# Main_Board_Motor_Control.net
KiCad netlist of a schematic drawn in Altium Designer
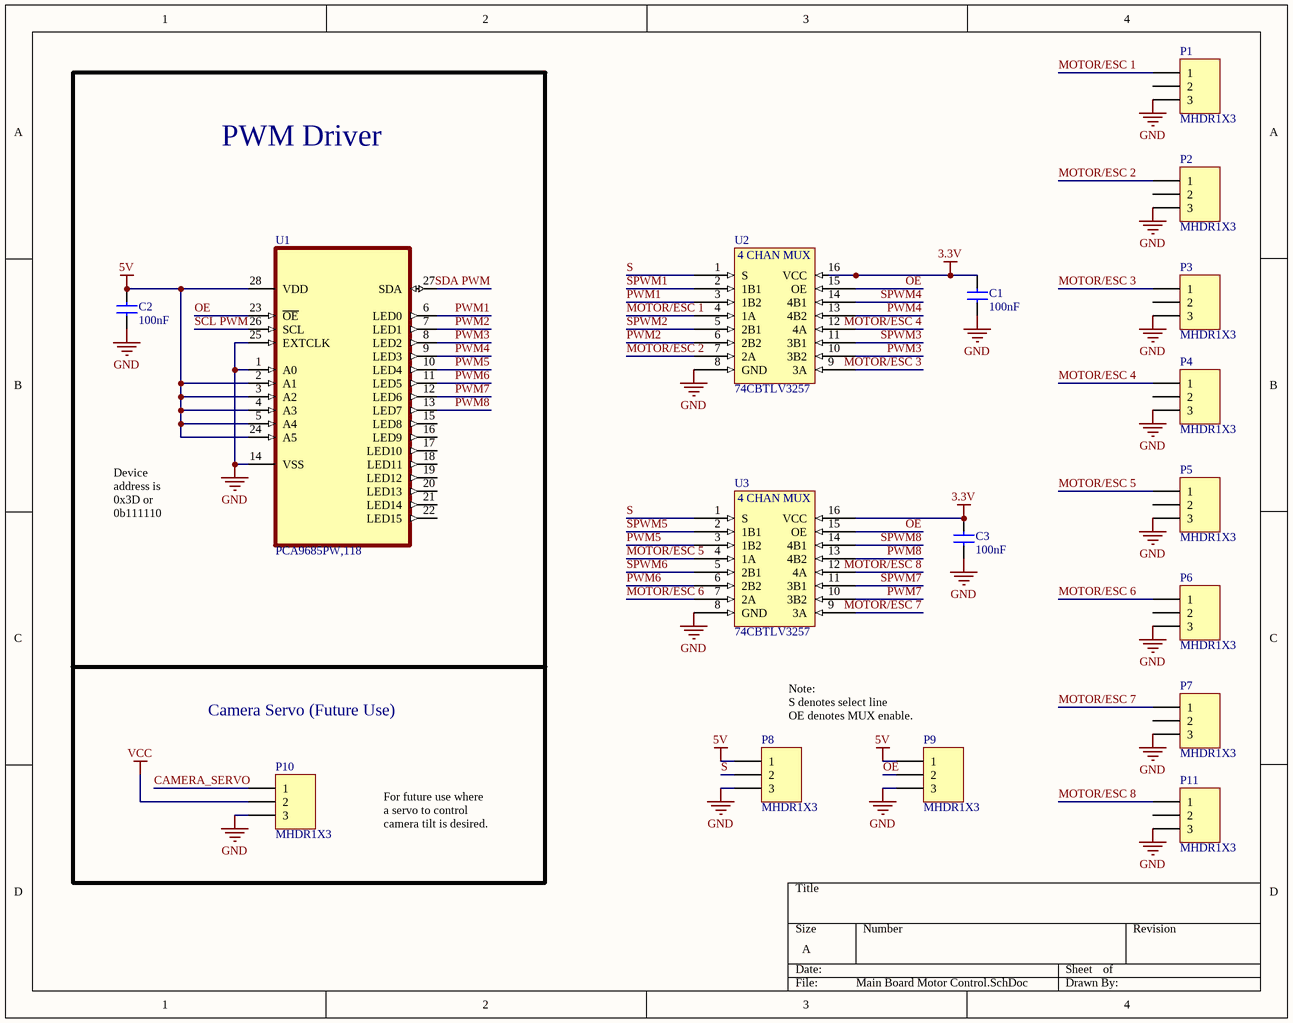
[diagram p0: Main Board Motor Control.SchDoc]

(export (version "E")
  (design (tool "Eeschema 10.0.6"))
  (components
    (comp (ref "C1")
      (value "100nF")
      (footprint "CAPC0603")
      (fields (field (name "Comment") "Cap"))
      (libsource (lib "Passives") (part "Cap"))
    )
    (comp (ref "C2")
      (value "100nF")
      (footprint "CAPC0603")
      (fields (field (name "Comment") "Cap"))
      (libsource (lib "Passives") (part "Cap"))
    )
    (comp (ref "C3")
      (value "100nF")
      (footprint "CAPC0603")
      (fields (field (name "Comment") "Cap"))
      (libsource (lib "Passives") (part "Cap"))
    )
    (comp (ref "P1")
      (value "MHDR1X3")
      (footprint "MHDR1X3")
      (description "Header, 3-Pin")
      (fields (field (name "PUBLISHER") "Altium Limited"))
      (libsource (lib "Miscellaneous Connectors") (part "MHDR1X3"))
    )
    (comp (ref "P2")
      (value "MHDR1X3")
      (footprint "MHDR1X3")
      (description "Header, 3-Pin")
      (fields (field (name "PUBLISHER") "Altium Limited"))
      (libsource (lib "Miscellaneous Connectors") (part "MHDR1X3"))
    )
    (comp (ref "P3")
      (value "MHDR1X3")
      (footprint "MHDR1X3")
      (description "Header, 3-Pin")
      (fields (field (name "PUBLISHER") "Altium Limited"))
      (libsource (lib "Miscellaneous Connectors") (part "MHDR1X3"))
    )
    (comp (ref "P4")
      (value "MHDR1X3")
      (footprint "MHDR1X3")
      (description "Header, 3-Pin")
      (fields (field (name "PUBLISHER") "Altium Limited"))
      (libsource (lib "Miscellaneous Connectors") (part "MHDR1X3"))
    )
    (comp (ref "P5")
      (value "MHDR1X3")
      (footprint "MHDR1X3")
      (description "Header, 3-Pin")
      (fields (field (name "PUBLISHER") "Altium Limited"))
      (libsource (lib "Miscellaneous Connectors") (part "MHDR1X3"))
    )
    (comp (ref "P6")
      (value "MHDR1X3")
      (footprint "MHDR1X3")
      (description "Header, 3-Pin")
      (fields (field (name "PUBLISHER") "Altium Limited"))
      (libsource (lib "Miscellaneous Connectors") (part "MHDR1X3"))
    )
    (comp (ref "P7")
      (value "MHDR1X3")
      (footprint "MHDR1X3")
      (description "Header, 3-Pin")
      (fields (field (name "PUBLISHER") "Altium Limited"))
      (libsource (lib "Miscellaneous Connectors") (part "MHDR1X3"))
    )
    (comp (ref "P8")
      (value "MHDR1X3")
      (footprint "MHDR1X3")
      (description "Header, 3-Pin")
      (fields (field (name "PUBLISHER") "Altium Limited"))
      (libsource (lib "Miscellaneous Connectors") (part "MHDR1X3"))
    )
    (comp (ref "P9")
      (value "MHDR1X3")
      (footprint "MHDR1X3")
      (description "Header, 3-Pin")
      (fields (field (name "PUBLISHER") "Altium Limited"))
      (libsource (lib "Miscellaneous Connectors") (part "MHDR1X3"))
    )
    (comp (ref "P10")
      (value "MHDR1X3")
      (footprint "MHDR1X3")
      (description "Header, 3-Pin")
      (fields (field (name "PUBLISHER") "Altium Limited"))
      (libsource (lib "Miscellaneous Connectors") (part "MHDR1X3"))
    )
    (comp (ref "P11")
      (value "MHDR1X3")
      (footprint "MHDR1X3")
      (description "Header, 3-Pin")
      (fields (field (name "PUBLISHER") "Altium Limited"))
      (libsource (lib "Miscellaneous Connectors") (part "MHDR1X3"))
    )
    (comp (ref "U1")
      (value "PCA9685PW,118")
      (footprint "SOP65P640X110-28N")
      (description "LED Driver IC 16 Output Linear - PWM Dimming 25mA 28-TSSOP")
      (fields (field (name "MF") "NXP USA"))
      (libsource (lib "ICs") (part "PCA9685PW,118"))
    )
    (comp (ref "U2")
      (value "74CBTLV3257")
      (footprint "TSSOP16")
      (description "Mux; 4 channel; 2:1; Demux")
      (libsource (lib "ICs") (part "74CBTLV3257"))
    )
    (comp (ref "U3")
      (value "74CBTLV3257")
      (footprint "TSSOP16")
      (description "Mux; 4 channel; 2:1; Demux")
      (libsource (lib "ICs") (part "74CBTLV3257"))
    )
  )
  (nets
    (net (code "1") (name "/CAMERA_SERVO") (class "Default")
      (node (ref "P10") (pin "1") (pinfunction "1_1") (pintype "passive"))
    )
    (net (code "2") (name "/MOTOR{slash}ESC 1") (class "Default")
      (node (ref "P1") (pin "1") (pinfunction "1_1") (pintype "passive"))
      (node (ref "U2") (pin "4") (pinfunction "1A_4") (pintype "input"))
    )
    (net (code "3") (name "/MOTOR{slash}ESC 2") (class "Default")
      (node (ref "P2") (pin "1") (pinfunction "1_1") (pintype "passive"))
      (node (ref "U2") (pin "7") (pinfunction "2A_7") (pintype "input"))
    )
    (net (code "4") (name "/MOTOR{slash}ESC 3") (class "Default")
      (node (ref "P3") (pin "1") (pinfunction "1_1") (pintype "passive"))
      (node (ref "U2") (pin "9") (pinfunction "3A_9") (pintype "input"))
    )
    (net (code "5") (name "/MOTOR{slash}ESC 4") (class "Default")
      (node (ref "P4") (pin "1") (pinfunction "1_1") (pintype "passive"))
      (node (ref "U2") (pin "12") (pinfunction "4A_12") (pintype "input"))
    )
    (net (code "6") (name "/MOTOR{slash}ESC 5") (class "Default")
      (node (ref "P5") (pin "1") (pinfunction "1_1") (pintype "passive"))
      (node (ref "U3") (pin "4") (pinfunction "1A_4") (pintype "input"))
    )
    (net (code "7") (name "/MOTOR{slash}ESC 6") (class "Default")
      (node (ref "P6") (pin "1") (pinfunction "1_1") (pintype "passive"))
      (node (ref "U3") (pin "7") (pinfunction "2A_7") (pintype "input"))
    )
    (net (code "8") (name "/MOTOR{slash}ESC 7") (class "Default")
      (node (ref "P7") (pin "1") (pinfunction "1_1") (pintype "passive"))
      (node (ref "U3") (pin "9") (pinfunction "3A_9") (pintype "input"))
    )
    (net (code "9") (name "/MOTOR{slash}ESC 8") (class "Default")
      (node (ref "P11") (pin "1") (pinfunction "1_1") (pintype "passive"))
      (node (ref "U3") (pin "12") (pinfunction "4A_12") (pintype "input"))
    )
    (net (code "10") (name "/OE") (class "Default")
      (node (ref "P9") (pin "2") (pinfunction "2_2") (pintype "passive"))
      (node (ref "U1") (pin "23") (pinfunction "~{OE}_23") (pintype "input"))
      (node (ref "U2") (pin "15") (pinfunction "OE_15") (pintype "input"))
      (node (ref "U3") (pin "15") (pinfunction "OE_15") (pintype "input"))
    )
    (net (code "11") (name "/PWM1") (class "Default")
      (node (ref "U1") (pin "6") (pinfunction "LED0_6") (pintype "output"))
      (node (ref "U2") (pin "3") (pinfunction "1B2_3") (pintype "input"))
    )
    (net (code "12") (name "/PWM2") (class "Default")
      (node (ref "U1") (pin "7") (pinfunction "LED1_7") (pintype "output"))
      (node (ref "U2") (pin "6") (pinfunction "2B2_6") (pintype "input"))
    )
    (net (code "13") (name "/PWM3") (class "Default")
      (node (ref "U1") (pin "8") (pinfunction "LED2_8") (pintype "output"))
      (node (ref "U2") (pin "10") (pinfunction "3B2_10") (pintype "input"))
    )
    (net (code "14") (name "/PWM4") (class "Default")
      (node (ref "U1") (pin "9") (pinfunction "LED3_9") (pintype "output"))
      (node (ref "U2") (pin "13") (pinfunction "4B2_13") (pintype "input"))
    )
    (net (code "15") (name "/PWM5") (class "Default")
      (node (ref "U1") (pin "10") (pinfunction "LED4_10") (pintype "output"))
      (node (ref "U3") (pin "3") (pinfunction "1B2_3") (pintype "input"))
    )
    (net (code "16") (name "/PWM6") (class "Default")
      (node (ref "U1") (pin "11") (pinfunction "LED5_11") (pintype "output"))
      (node (ref "U3") (pin "6") (pinfunction "2B2_6") (pintype "input"))
    )
    (net (code "17") (name "/PWM7") (class "Default")
      (node (ref "U1") (pin "12") (pinfunction "LED6_12") (pintype "output"))
      (node (ref "U3") (pin "10") (pinfunction "3B2_10") (pintype "input"))
    )
    (net (code "18") (name "/PWM8") (class "Default")
      (node (ref "U1") (pin "13") (pinfunction "LED7_13") (pintype "output"))
      (node (ref "U3") (pin "13") (pinfunction "4B2_13") (pintype "input"))
    )
    (net (code "19") (name "/S") (class "Default")
      (node (ref "P8") (pin "2") (pinfunction "2_2") (pintype "passive"))
      (node (ref "U2") (pin "1") (pinfunction "S_1") (pintype "input"))
      (node (ref "U3") (pin "1") (pinfunction "S_1") (pintype "input"))
    )
    (net (code "20") (name "/SCL PWM") (class "Default")
      (node (ref "U1") (pin "26") (pinfunction "SCL_26") (pintype "input"))
    )
    (net (code "21") (name "/SDA PWM") (class "Default")
      (node (ref "U1") (pin "27") (pinfunction "SDA_27") (pintype "bidirectional"))
    )
    (net (code "22") (name "/SPWM1") (class "Default")
      (node (ref "U2") (pin "2") (pinfunction "1B1_2") (pintype "input"))
    )
    (net (code "23") (name "/SPWM2") (class "Default")
      (node (ref "U2") (pin "5") (pinfunction "2B1_5") (pintype "input"))
    )
    (net (code "24") (name "/SPWM3") (class "Default")
      (node (ref "U2") (pin "11") (pinfunction "3B1_11") (pintype "input"))
    )
    (net (code "25") (name "/SPWM4") (class "Default")
      (node (ref "U2") (pin "14") (pinfunction "4B1_14") (pintype "input"))
    )
    (net (code "26") (name "/SPWM5") (class "Default")
      (node (ref "U3") (pin "2") (pinfunction "1B1_2") (pintype "input"))
    )
    (net (code "27") (name "/SPWM6") (class "Default")
      (node (ref "U3") (pin "5") (pinfunction "2B1_5") (pintype "input"))
    )
    (net (code "28") (name "/SPWM7") (class "Default")
      (node (ref "U3") (pin "11") (pinfunction "3B1_11") (pintype "input"))
    )
    (net (code "29") (name "/SPWM8") (class "Default")
      (node (ref "U3") (pin "14") (pinfunction "4B1_14") (pintype "input"))
    )
    (net (code "30") (name "3.3V") (class "Default")
      (node (ref "C1") (pin "1") (pinfunction "A_1") (pintype "passive"))
      (node (ref "C3") (pin "1") (pinfunction "A_1") (pintype "passive"))
      (node (ref "U2") (pin "16") (pinfunction "VCC_16") (pintype "input"))
      (node (ref "U3") (pin "16") (pinfunction "VCC_16") (pintype "input"))
    )
    (net (code "31") (name "5V") (class "Default")
      (node (ref "C2") (pin "1") (pinfunction "A_1") (pintype "passive"))
      (node (ref "P8") (pin "1") (pinfunction "1_1") (pintype "passive"))
      (node (ref "P9") (pin "1") (pinfunction "1_1") (pintype "passive"))
      (node (ref "U1") (pin "2") (pinfunction "A1_2") (pintype "input"))
      (node (ref "U1") (pin "24") (pinfunction "A5_24") (pintype "input"))
      (node (ref "U1") (pin "28") (pinfunction "VDD_28") (pintype "power_in"))
      (node (ref "U1") (pin "3") (pinfunction "A2_3") (pintype "input"))
      (node (ref "U1") (pin "4") (pinfunction "A3_4") (pintype "input"))
      (node (ref "U1") (pin "5") (pinfunction "A4_5") (pintype "input"))
    )
    (net (code "32") (name "GND") (class "Default")
      (node (ref "C1") (pin "2") (pinfunction "B_2") (pintype "passive"))
      (node (ref "C2") (pin "2") (pinfunction "B_2") (pintype "passive"))
      (node (ref "C3") (pin "2") (pinfunction "B_2") (pintype "passive"))
      (node (ref "P1") (pin "3") (pinfunction "3_3") (pintype "passive"))
      (node (ref "P10") (pin "3") (pinfunction "3_3") (pintype "passive"))
      (node (ref "P11") (pin "3") (pinfunction "3_3") (pintype "passive"))
      (node (ref "P2") (pin "3") (pinfunction "3_3") (pintype "passive"))
      (node (ref "P3") (pin "3") (pinfunction "3_3") (pintype "passive"))
      (node (ref "P4") (pin "3") (pinfunction "3_3") (pintype "passive"))
      (node (ref "P5") (pin "3") (pinfunction "3_3") (pintype "passive"))
      (node (ref "P6") (pin "3") (pinfunction "3_3") (pintype "passive"))
      (node (ref "P7") (pin "3") (pinfunction "3_3") (pintype "passive"))
      (node (ref "P8") (pin "3") (pinfunction "3_3") (pintype "passive"))
      (node (ref "P9") (pin "3") (pinfunction "3_3") (pintype "passive"))
      (node (ref "U1") (pin "1") (pinfunction "A0_1") (pintype "input"))
      (node (ref "U1") (pin "14") (pinfunction "VSS_14") (pintype "passive"))
      (node (ref "U1") (pin "25") (pinfunction "EXTCLK_25") (pintype "input"))
      (node (ref "U2") (pin "8") (pinfunction "GND_8") (pintype "input"))
      (node (ref "U3") (pin "8") (pinfunction "GND_8") (pintype "input"))
    )
    (net (code "33") (name "VCC") (class "Default")
      (node (ref "P10") (pin "2") (pinfunction "2_2") (pintype "passive"))
    )
    (net (code "34") (name "unconnected-(P1-Pad2)") (class "Default")
      (node (ref "P1") (pin "2") (pinfunction "2_2") (pintype "passive"))
    )
    (net (code "35") (name "unconnected-(P2-Pad2)") (class "Default")
      (node (ref "P2") (pin "2") (pinfunction "2_2") (pintype "passive"))
    )
    (net (code "36") (name "unconnected-(P3-Pad2)") (class "Default")
      (node (ref "P3") (pin "2") (pinfunction "2_2") (pintype "passive"))
    )
    (net (code "37") (name "unconnected-(P4-Pad2)") (class "Default")
      (node (ref "P4") (pin "2") (pinfunction "2_2") (pintype "passive"))
    )
    (net (code "38") (name "unconnected-(P5-Pad2)") (class "Default")
      (node (ref "P5") (pin "2") (pinfunction "2_2") (pintype "passive"))
    )
    (net (code "39") (name "unconnected-(P6-Pad2)") (class "Default")
      (node (ref "P6") (pin "2") (pinfunction "2_2") (pintype "passive"))
    )
    (net (code "40") (name "unconnected-(P7-Pad2)") (class "Default")
      (node (ref "P7") (pin "2") (pinfunction "2_2") (pintype "passive"))
    )
    (net (code "41") (name "unconnected-(P11-Pad2)") (class "Default")
      (node (ref "P11") (pin "2") (pinfunction "2_2") (pintype "passive"))
    )
    (net (code "42") (name "unconnected-(U1-LED8-Pad15)") (class "Default")
      (node (ref "U1") (pin "15") (pinfunction "LED8_15") (pintype "output"))
    )
    (net (code "43") (name "unconnected-(U1-LED9-Pad16)") (class "Default")
      (node (ref "U1") (pin "16") (pinfunction "LED9_16") (pintype "output"))
    )
    (net (code "44") (name "unconnected-(U1-LED10-Pad17)") (class "Default")
      (node (ref "U1") (pin "17") (pinfunction "LED10_17") (pintype "output"))
    )
    (net (code "45") (name "unconnected-(U1-LED11-Pad18)") (class "Default")
      (node (ref "U1") (pin "18") (pinfunction "LED11_18") (pintype "output"))
    )
    (net (code "46") (name "unconnected-(U1-LED12-Pad19)") (class "Default")
      (node (ref "U1") (pin "19") (pinfunction "LED12_19") (pintype "output"))
    )
    (net (code "47") (name "unconnected-(U1-LED13-Pad20)") (class "Default")
      (node (ref "U1") (pin "20") (pinfunction "LED13_20") (pintype "output"))
    )
    (net (code "48") (name "unconnected-(U1-LED14-Pad21)") (class "Default")
      (node (ref "U1") (pin "21") (pinfunction "LED14_21") (pintype "output"))
    )
    (net (code "49") (name "unconnected-(U1-LED15-Pad22)") (class "Default")
      (node (ref "U1") (pin "22") (pinfunction "LED15_22") (pintype "output"))
    )
  )
)
